# lolin_lite.net
KiCad netlist of a schematic drawn in EAGLE
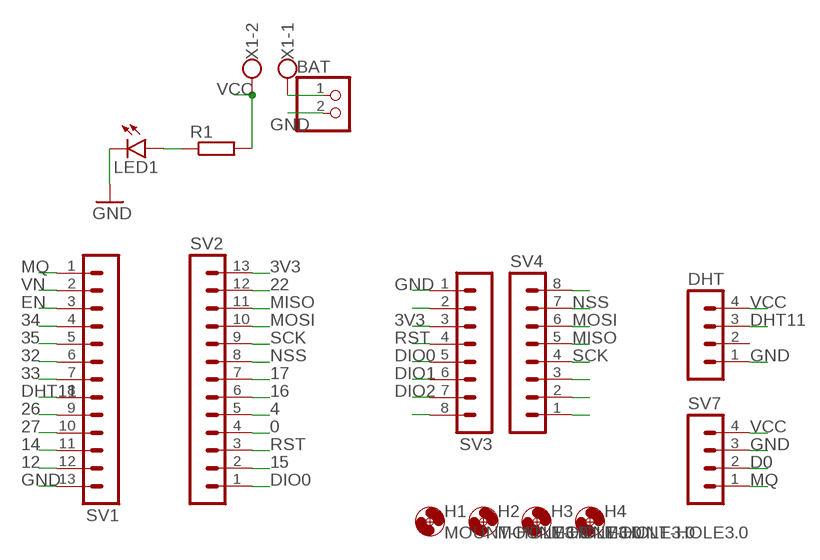
[diagram p0: schematic, sheet 1]

(export (version "E")
  (design (tool "Eeschema 10.0.6"))
  (components
    (comp (ref "BAT")
      (value "PINHD-1X2")
      (footprint "eagle-import:1X02")
      (libsource (lib "eagle-import") (part "PINHD-1X2"))
    )
    (comp (ref "DHT")
      (value "MA04-1")
      (footprint "eagle-import:MA04-1")
      (libsource (lib "eagle-import") (part "MA04-1"))
    )
    (comp (ref "H1")
      (value "MOUNT-HOLE3.0")
      (footprint "eagle-import:3,0")
      (libsource (lib "eagle-import") (part "MOUNT-HOLE3.0"))
    )
    (comp (ref "H2")
      (value "MOUNT-HOLE3.0")
      (footprint "eagle-import:3,0")
      (libsource (lib "eagle-import") (part "MOUNT-HOLE3.0"))
    )
    (comp (ref "H3")
      (value "MOUNT-HOLE3.0")
      (footprint "eagle-import:3,0")
      (libsource (lib "eagle-import") (part "MOUNT-HOLE3.0"))
    )
    (comp (ref "H4")
      (value "MOUNT-HOLE3.0")
      (footprint "eagle-import:3,0")
      (libsource (lib "eagle-import") (part "MOUNT-HOLE3.0"))
    )
    (comp (ref "LED1")
      (value "LED5MM")
      (footprint "eagle-import:LED5MM")
      (libsource (lib "eagle-import") (part "LED5MM"))
    )
    (comp (ref "R1")
      (value "R-EU_0309/10")
      (footprint "eagle-import:0309_10")
      (libsource (lib "eagle-import") (part "R-EU_0309/10"))
    )
    (comp (ref "SV1")
      (value "MA13-1")
      (footprint "eagle-import:MA13-1")
      (libsource (lib "eagle-import") (part "MA13-1"))
    )
    (comp (ref "SV2")
      (value "MA13-1")
      (footprint "eagle-import:MA13-1")
      (libsource (lib "eagle-import") (part "MA13-1"))
    )
    (comp (ref "SV3")
      (value "MA08-1")
      (footprint "eagle-import:MA08-1")
      (libsource (lib "eagle-import") (part "MA08-1"))
    )
    (comp (ref "SV4")
      (value "MA08-1")
      (footprint "eagle-import:MA08-1")
      (libsource (lib "eagle-import") (part "MA08-1"))
    )
    (comp (ref "SV7")
      (value "MA04-1")
      (footprint "eagle-import:MA04-1")
      (libsource (lib "eagle-import") (part "MA04-1"))
    )
    (comp (ref "X1")
      (value "W237-102")
      (footprint "eagle-import:W237-102")
      (fields (field (name "MPN") "237-102"))
      (libsource (lib "eagle-import") (part "W237-102"))
    )
  )
  (nets
    (net (code "1") (name "/0") (class "Default")
      (node (ref "SV2") (pin "4") (pinfunction "4_4") (pintype "passive"))
    )
    (net (code "2") (name "/3V3") (class "Default")
      (node (ref "SV2") (pin "13") (pinfunction "13_13") (pintype "passive"))
      (node (ref "SV3") (pin "3") (pinfunction "3_3") (pintype "passive"))
    )
    (net (code "3") (name "/4") (class "Default")
      (node (ref "SV2") (pin "5") (pinfunction "5_5") (pintype "passive"))
    )
    (net (code "4") (name "/12") (class "Default")
      (node (ref "SV1") (pin "12") (pinfunction "12_12") (pintype "passive"))
    )
    (net (code "5") (name "/14") (class "Default")
      (node (ref "SV1") (pin "11") (pinfunction "11_11") (pintype "passive"))
    )
    (net (code "6") (name "/15") (class "Default")
      (node (ref "SV2") (pin "2") (pinfunction "2_2") (pintype "passive"))
    )
    (net (code "7") (name "/16") (class "Default")
      (node (ref "SV2") (pin "6") (pinfunction "6_6") (pintype "passive"))
    )
    (net (code "8") (name "/17") (class "Default")
      (node (ref "SV2") (pin "7") (pinfunction "7_7") (pintype "passive"))
    )
    (net (code "9") (name "/22") (class "Default")
      (node (ref "SV2") (pin "12") (pinfunction "12_12") (pintype "passive"))
    )
    (net (code "10") (name "/26") (class "Default")
      (node (ref "SV1") (pin "9") (pinfunction "9_9") (pintype "passive"))
    )
    (net (code "11") (name "/27") (class "Default")
      (node (ref "SV1") (pin "10") (pinfunction "10_10") (pintype "passive"))
    )
    (net (code "12") (name "/32") (class "Default")
      (node (ref "SV1") (pin "6") (pinfunction "6_6") (pintype "passive"))
    )
    (net (code "13") (name "/33") (class "Default")
      (node (ref "SV1") (pin "7") (pinfunction "7_7") (pintype "passive"))
    )
    (net (code "14") (name "/34") (class "Default")
      (node (ref "SV1") (pin "4") (pinfunction "4_4") (pintype "passive"))
    )
    (net (code "15") (name "/35") (class "Default")
      (node (ref "SV1") (pin "5") (pinfunction "5_5") (pintype "passive"))
    )
    (net (code "16") (name "/D0") (class "Default")
      (node (ref "SV7") (pin "2") (pinfunction "2_2") (pintype "passive"))
    )
    (net (code "17") (name "/DHT11") (class "Default")
      (node (ref "DHT") (pin "3") (pinfunction "3_3") (pintype "passive"))
      (node (ref "SV1") (pin "8") (pinfunction "8_8") (pintype "passive"))
    )
    (net (code "18") (name "/DIO0") (class "Default")
      (node (ref "SV2") (pin "1") (pinfunction "1_1") (pintype "passive"))
      (node (ref "SV3") (pin "5") (pinfunction "5_5") (pintype "passive"))
    )
    (net (code "19") (name "/DIO1") (class "Default")
      (node (ref "SV3") (pin "6") (pinfunction "6_6") (pintype "passive"))
    )
    (net (code "20") (name "/DIO2") (class "Default")
      (node (ref "SV3") (pin "7") (pinfunction "7_7") (pintype "passive"))
    )
    (net (code "21") (name "/EN") (class "Default")
      (node (ref "SV1") (pin "3") (pinfunction "3_3") (pintype "passive"))
    )
    (net (code "22") (name "/MISO") (class "Default")
      (node (ref "SV2") (pin "11") (pinfunction "11_11") (pintype "passive"))
      (node (ref "SV4") (pin "5") (pinfunction "5_5") (pintype "passive"))
    )
    (net (code "23") (name "/MOSI") (class "Default")
      (node (ref "SV2") (pin "10") (pinfunction "10_10") (pintype "passive"))
      (node (ref "SV4") (pin "6") (pinfunction "6_6") (pintype "passive"))
    )
    (net (code "24") (name "/MQ") (class "Default")
      (node (ref "SV1") (pin "1") (pinfunction "1_1") (pintype "passive"))
      (node (ref "SV7") (pin "1") (pinfunction "1_1") (pintype "passive"))
    )
    (net (code "25") (name "/NSS") (class "Default")
      (node (ref "SV2") (pin "8") (pinfunction "8_8") (pintype "passive"))
      (node (ref "SV4") (pin "7") (pinfunction "7_7") (pintype "passive"))
    )
    (net (code "26") (name "/RST") (class "Default")
      (node (ref "SV2") (pin "3") (pinfunction "3_3") (pintype "passive"))
      (node (ref "SV3") (pin "4") (pinfunction "4_4") (pintype "passive"))
    )
    (net (code "27") (name "/SCK") (class "Default")
      (node (ref "SV2") (pin "9") (pinfunction "9_9") (pintype "passive"))
      (node (ref "SV4") (pin "4") (pinfunction "4_4") (pintype "passive"))
    )
    (net (code "28") (name "/VCC") (class "Default")
      (node (ref "DHT") (pin "4") (pinfunction "4_4") (pintype "passive"))
      (node (ref "R1") (pin "2") (pinfunction "2_2") (pintype "passive"))
      (node (ref "SV7") (pin "4") (pinfunction "4_4") (pintype "passive"))
      (node (ref "X1") (pin "2") (pinfunction "KL_2") (pintype "passive"))
    )
    (net (code "29") (name "/VN") (class "Default")
      (node (ref "SV1") (pin "2") (pinfunction "2_2") (pintype "passive"))
    )
    (net (code "30") (name "GND") (class "Default")
      (node (ref "BAT") (pin "2") (pinfunction "2_2") (pintype "passive"))
      (node (ref "DHT") (pin "1") (pinfunction "1_1") (pintype "passive"))
      (node (ref "LED1") (pin "K") (pinfunction "C_K") (pintype "passive"))
      (node (ref "SV1") (pin "13") (pinfunction "13_13") (pintype "passive"))
      (node (ref "SV3") (pin "1") (pinfunction "1_1") (pintype "passive"))
      (node (ref "SV7") (pin "3") (pinfunction "3_3") (pintype "passive"))
    )
    (net (code "31") (name "Net-(LED1-PadA)") (class "Default")
      (node (ref "LED1") (pin "A") (pinfunction "A_A") (pintype "passive"))
      (node (ref "R1") (pin "1") (pinfunction "1_1") (pintype "passive"))
    )
    (net (code "32") (name "Net-(X1A-KL)") (class "Default")
      (node (ref "BAT") (pin "1") (pinfunction "1_1") (pintype "passive"))
      (node (ref "X1") (pin "1") (pinfunction "KL_1") (pintype "passive"))
    )
    (net (code "33") (name "unconnected-(DHT-Pad2)") (class "Default")
      (node (ref "DHT") (pin "2") (pinfunction "2_2") (pintype "passive"))
    )
    (net (code "34") (name "unconnected-(SV3-Pad2)") (class "Default")
      (node (ref "SV3") (pin "2") (pinfunction "2_2") (pintype "passive"))
    )
    (net (code "35") (name "unconnected-(SV3-Pad8)") (class "Default")
      (node (ref "SV3") (pin "8") (pinfunction "8_8") (pintype "passive"))
    )
    (net (code "36") (name "unconnected-(SV4-Pad1)") (class "Default")
      (node (ref "SV4") (pin "1") (pinfunction "1_1") (pintype "passive"))
    )
    (net (code "37") (name "unconnected-(SV4-Pad2)") (class "Default")
      (node (ref "SV4") (pin "2") (pinfunction "2_2") (pintype "passive"))
    )
    (net (code "38") (name "unconnected-(SV4-Pad3)") (class "Default")
      (node (ref "SV4") (pin "3") (pinfunction "3_3") (pintype "passive"))
    )
    (net (code "39") (name "unconnected-(SV4-Pad8)") (class "Default")
      (node (ref "SV4") (pin "8") (pinfunction "8_8") (pintype "passive"))
    )
  )
)
